# mcu.net
KiCad netlist of a schematic drawn in Altium Designer
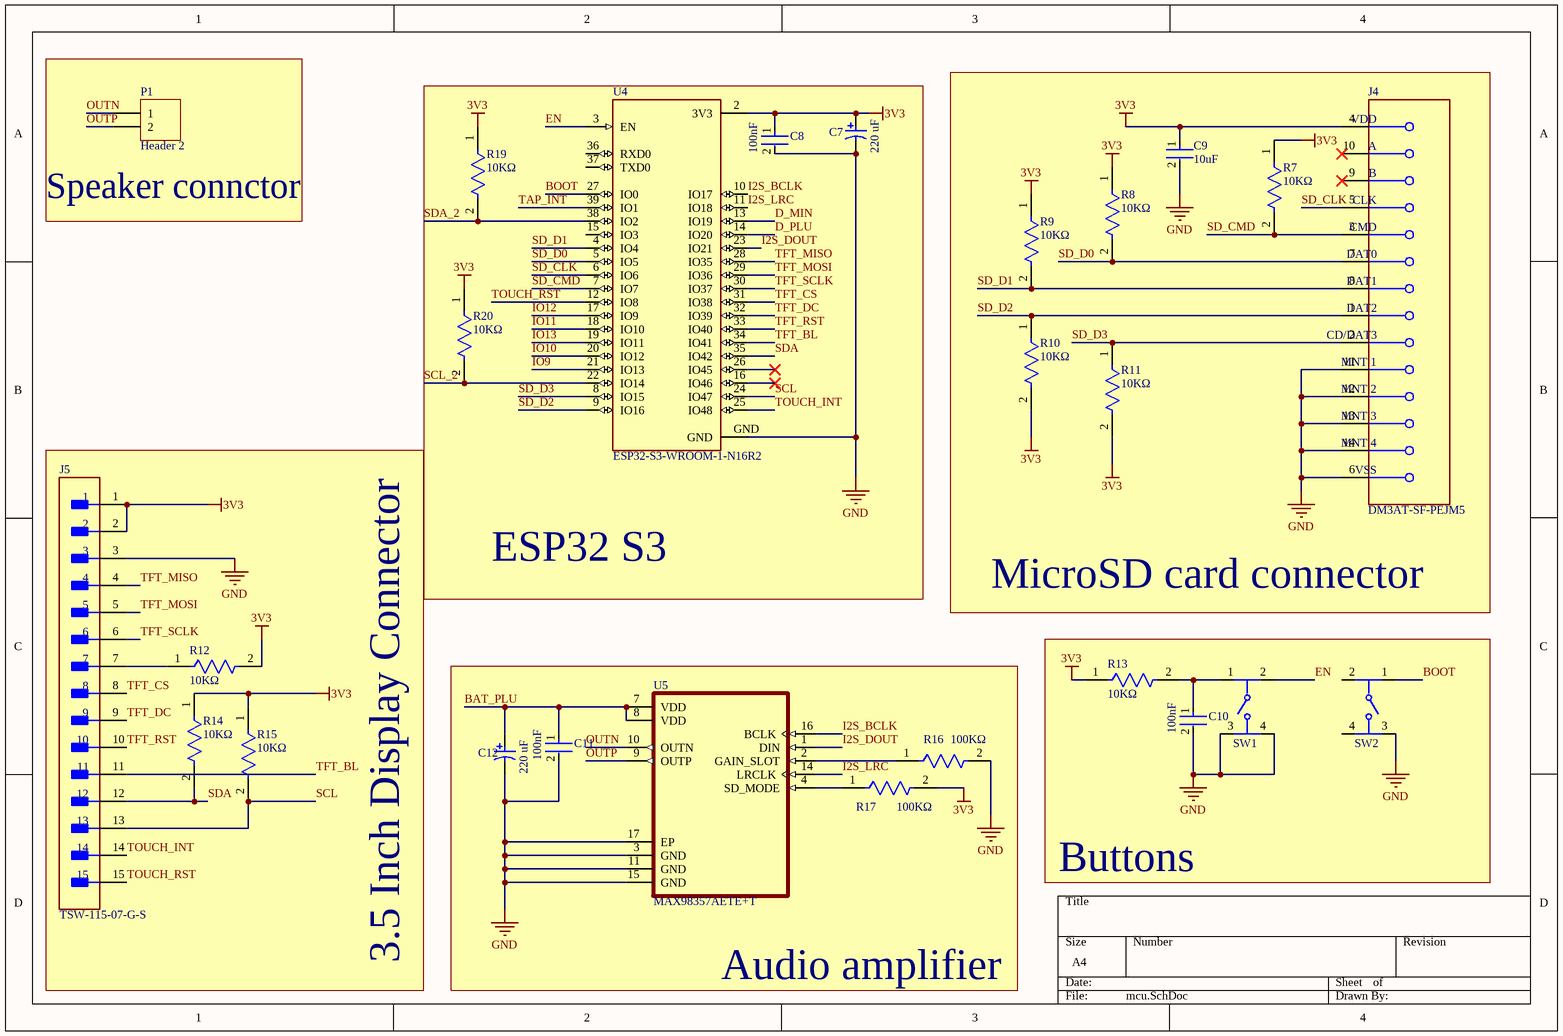
[diagram p0: mcu.SchDoc]

(export (version "E")
  (design (tool "Eeschema 10.0.6"))
  (components
    (comp (ref "C7")
      (value "UUD1V221MNL1GS")
      (footprint "NIC-CAPA2-8X10_V")
      (fields
        (field (name "RATED CAPACITANCE") "220 uF")
        (field (name "MANUFACTURER") "Nichicon")
        (field (name "LCSC PART") "C2836441")
      )
      (libsource (lib "Altium Content Vault") (part "NIC-CAP-P-2"))
    )
    (comp (ref "C8")
      (value "CC0805KKX7RYBB104")
      (footprint "FP-CC0805-EB-IPC_B")
      (description "CC0805KKX7RYBB104 Capacitor Ceramic 0.01uF 250V X7R 10% 0805 T/R")
      (fields
        (field (name "TOLERANCE") "10%")
        (field (name "CAPACITANCE") "100nF")
        (field (name "LCSC PART") "C28233")
      )
      (libsource (lib "Altium Content Vault") (part "b4654b650e69147ec39a6b967a45e02"))
    )
    (comp (ref "C9")
      (value "C0805C106J8RACAUTO")
      (footprint "FP-C0805C106J8RACAUTO-IPC_B")
      (description "CAP CER 10UF 10V X7R 0805")
      (fields
        (field (name "CAPACITANCE") "10uF")
        (field (name "TOLERANCE") "5%")
        (field (name "LCSC PART") "C15850")
      )
      (libsource (lib "Altium Content Vault") (part "02cd4be3c70576c341d710602a673aa"))
    )
    (comp (ref "C10")
      (value "CC0805KKX7RYBB104")
      (footprint "FP-CC0805-EB-IPC_B")
      (description "CC0805KKX7RYBB104 Capacitor Ceramic 0.01uF 250V X7R 10% 0805 T/R")
      (fields
        (field (name "TOLERANCE") "10%")
        (field (name "CAPACITANCE") "100nF")
        (field (name "LCSC PART") "C28233")
      )
      (libsource (lib "Altium Content Vault") (part "b4654b650e69147ec39a6b967a45e02"))
    )
    (comp (ref "C11")
      (value "CC0805KKX7RYBB104")
      (footprint "FP-CC0805-EB-IPC_B")
      (description "CC0805KKX7RYBB104 Capacitor Ceramic 0.01uF 250V X7R 10% 0805 T/R")
      (fields
        (field (name "TOLERANCE") "10%")
        (field (name "CAPACITANCE") "100nF")
        (field (name "LCSC PART") "C28233")
      )
      (libsource (lib "Altium Content Vault") (part "b4654b650e69147ec39a6b967a45e02"))
    )
    (comp (ref "C12")
      (value "UUD1V221MNL1GS")
      (footprint "NIC-CAPA2-8X10_V")
      (fields
        (field (name "RATED CAPACITANCE") "220 uF")
        (field (name "MANUFACTURER") "Nichicon")
        (field (name "LCSC PART") "C2836441")
      )
      (libsource (lib "Altium Content Vault") (part "NIC-CAP-P-2"))
    )
    (comp (ref "J4")
      (value "DM3AT-SF-PEJM5")
      (footprint "FP-DM3AT-SF-PEJM5-MFG")
      (description "CONN MICRO SD CARD PUSH-PUSH R/A")
      (fields (field (name "LCSC PART") "C114218"))
      (libsource (lib "Altium Content Vault") (part "a4e64ec0820c4377148bc1329e4c440"))
    )
    (comp (ref "J5")
      (value "TSW-115-07-G-S")
      (footprint "FP-TSW-115-07-G-S-MFG")
      (description "CONN HEADER VERT 15POS 2.54MM")
      (fields
        (field (name "OCTOPART") "https://octopart.com/tsw-115-07-g-s-samtec-272210")
        (field (name "MANUFACTURER") "SAMTEC")
      )
      (libsource (lib "Altium Content Vault") (part "9e54aee09c46527fb07af492d4d8164"))
    )
    (comp (ref "P1")
      (value "Header 2")
      (footprint "HDR1X2")
      (description "Header, 2-Pin")
      (fields (field (name "LCSC PART") "C32713268") (field (name "PUBLISHER") "Altium Limited"))
      (libsource (lib "Miscellaneous Connectors") (part "Header 2"))
    )
    (comp (ref "R7")
      (value "10KΩ")
      (footprint "FP-RT0805-IPC_B")
      (description "RES SMD 10K OHM 1% 1/8W 0805")
      (fields
        (field (name "OCTOPART") "https://octopart.com/rt0805frd0710kl-yageo-71399701")
        (field (name "TOLERANCE") "0.0001")
      )
      (libsource (lib "Altium Content Vault") (part "1029c3af85768c4190bb7ad29bc67b5"))
    )
    (comp (ref "R8")
      (value "10KΩ")
      (footprint "FP-RT0805-IPC_B")
      (description "RES SMD 10K OHM 1% 1/8W 0805")
      (fields
        (field (name "OCTOPART") "https://octopart.com/rt0805frd0710kl-yageo-71399701")
        (field (name "TOLERANCE") "0.0001")
      )
      (libsource (lib "Altium Content Vault") (part "1029c3af85768c4190bb7ad29bc67b5"))
    )
    (comp (ref "R9")
      (value "10KΩ")
      (footprint "FP-RT0805-IPC_B")
      (description "RES SMD 10K OHM 1% 1/8W 0805")
      (fields
        (field (name "OCTOPART") "https://octopart.com/rt0805frd0710kl-yageo-71399701")
        (field (name "TOLERANCE") "0.0001")
      )
      (libsource (lib "Altium Content Vault") (part "1029c3af85768c4190bb7ad29bc67b5"))
    )
    (comp (ref "R10")
      (value "10KΩ")
      (footprint "FP-RT0805-IPC_B")
      (description "RES SMD 10K OHM 1% 1/8W 0805")
      (fields
        (field (name "OCTOPART") "https://octopart.com/rt0805frd0710kl-yageo-71399701")
        (field (name "TOLERANCE") "0.0001")
      )
      (libsource (lib "Altium Content Vault") (part "1029c3af85768c4190bb7ad29bc67b5"))
    )
    (comp (ref "R11")
      (value "10KΩ")
      (footprint "FP-RT0805-IPC_B")
      (description "RES SMD 10K OHM 1% 1/8W 0805")
      (fields
        (field (name "OCTOPART") "https://octopart.com/rt0805frd0710kl-yageo-71399701")
        (field (name "TOLERANCE") "0.0001")
      )
      (libsource (lib "Altium Content Vault") (part "1029c3af85768c4190bb7ad29bc67b5"))
    )
    (comp (ref "R12")
      (value "10KΩ")
      (footprint "FP-RT0805-IPC_B")
      (description "RES SMD 10K OHM 1% 1/8W 0805")
      (fields
        (field (name "OCTOPART") "https://octopart.com/rt0805frd0710kl-yageo-71399701")
        (field (name "TOLERANCE") "0.0001")
      )
      (libsource (lib "Altium Content Vault") (part "1029c3af85768c4190bb7ad29bc67b5"))
    )
    (comp (ref "R13")
      (value "10KΩ")
      (footprint "FP-RT0805-IPC_B")
      (description "RES SMD 10K OHM 1% 1/8W 0805")
      (fields
        (field (name "OCTOPART") "https://octopart.com/rt0805frd0710kl-yageo-71399701")
        (field (name "TOLERANCE") "0.0001")
      )
      (libsource (lib "Altium Content Vault") (part "1029c3af85768c4190bb7ad29bc67b5"))
    )
    (comp (ref "R14")
      (value "10KΩ")
      (footprint "FP-RT0805-IPC_B")
      (description "RES SMD 10K OHM 1% 1/8W 0805")
      (fields
        (field (name "OCTOPART") "https://octopart.com/rt0805frd0710kl-yageo-71399701")
        (field (name "TOLERANCE") "0.0001")
      )
      (libsource (lib "Altium Content Vault") (part "1029c3af85768c4190bb7ad29bc67b5"))
    )
    (comp (ref "R15")
      (value "10KΩ")
      (footprint "FP-RT0805-IPC_B")
      (description "RES SMD 10K OHM 1% 1/8W 0805")
      (fields
        (field (name "OCTOPART") "https://octopart.com/rt0805frd0710kl-yageo-71399701")
        (field (name "TOLERANCE") "0.0001")
      )
      (libsource (lib "Altium Content Vault") (part "1029c3af85768c4190bb7ad29bc67b5"))
    )
    (comp (ref "R16")
      (value "100KΩ")
      (footprint "FP-RT0805-MFG")
      (description "RES SMD 100K OHM 0.5% 1/8W 0805")
      (fields
        (field (name "MANUFACTURER") "Yageo")
        (field (name "OCTOPART") "https://octopart.com/rt0805drd07100kl-yageo-1251654")
      )
      (libsource (lib "Altium Content Vault") (part "1029c3af85768c4190bb7ad29bc67b5"))
    )
    (comp (ref "R17")
      (value "100KΩ")
      (footprint "FP-RT0805-MFG")
      (description "RES SMD 100K OHM 0.5% 1/8W 0805")
      (fields
        (field (name "MANUFACTURER") "Yageo")
        (field (name "OCTOPART") "https://octopart.com/rt0805drd07100kl-yageo-1251654")
      )
      (libsource (lib "Altium Content Vault") (part "1029c3af85768c4190bb7ad29bc67b5"))
    )
    (comp (ref "R19")
      (value "10KΩ")
      (footprint "FP-RT0805-IPC_B")
      (description "RES SMD 10K OHM 1% 1/8W 0805")
      (fields
        (field (name "OCTOPART") "https://octopart.com/rt0805frd0710kl-yageo-71399701")
        (field (name "TOLERANCE") "0.0001")
      )
      (libsource (lib "Altium Content Vault") (part "1029c3af85768c4190bb7ad29bc67b5"))
    )
    (comp (ref "R20")
      (value "10KΩ")
      (footprint "FP-RT0805-IPC_B")
      (description "RES SMD 10K OHM 1% 1/8W 0805")
      (fields
        (field (name "OCTOPART") "https://octopart.com/rt0805frd0710kl-yageo-71399701")
        (field (name "TOLERANCE") "0.0001")
      )
      (libsource (lib "Altium Content Vault") (part "1029c3af85768c4190bb7ad29bc67b5"))
    )
    (comp (ref "SW1")
      (value "2-1977223-2")
      (footprint "FP-2-1977223-2-MFG")
      (description "SWITCH TACTILE SPST-NO 0.05A 24V")
      (fields (field (name "LCSC PART") "C557615"))
      (libsource (lib "Altium Content Vault") (part "b8895f3f4cefb76e1819d2863dba89b"))
    )
    (comp (ref "SW2")
      (value "2-1977223-2")
      (footprint "FP-2-1977223-2-MFG")
      (description "SWITCH TACTILE SPST-NO 0.05A 24V")
      (fields (field (name "LCSC PART") "C557615"))
      (libsource (lib "Altium Content Vault") (part "b8895f3f4cefb76e1819d2863dba89b"))
    )
    (comp (ref "U4")
      (value "ESP32-S3-WROOM-1-N16R2")
      (footprint "XCVR_ESP32-S3-WROOM-1-N16R2")
      (description "Bluetooth, WiFi 802.11b/g/n, Bluetooth v5.0 Transceiver Module 2.4GHz PCB Trace Surface Mount")
      (fields (field (name "MF") "Espressif Systems") (field (name "MP") "ESP32S3WROOM1N16R2"))
      (libsource (lib "ESP32-S3-WROOM-1-N16R2") (part "ESP32-S3-WROOM-1-N16R2"))
    )
    (comp (ref "U5")
      (value "MAX98357AETE+T")
      (footprint "QFN50P300X300X80-17N")
      (description "Tiny, Low-Cost, PCM Class D Amplifier with Class AB Performance")
      (fields (field (name "MF") "Analog Devices") (field (name "LCSC PART") "C910544"))
      (libsource (lib "MAX98357AETE_T") (part "MAX98357AETE+T"))
    )
  )
  (nets
    (net (code "1") (name "/BAT_PLU") (class "Default")
      (node (ref "C11") (pin "1") (pinfunction "1_1") (pintype "passive"))
      (node (ref "C12") (pin "1") (pinfunction "1_1") (pintype "passive"))
      (node (ref "U5") (pin "7") (pinfunction "VDD_7") (pintype "power_in"))
      (node (ref "U5") (pin "8") (pinfunction "VDD_8") (pintype "power_in"))
    )
    (net (code "2") (name "/BOOT") (class "Default")
      (node (ref "SW2") (pin "1") (pinfunction "1_1") (pintype "passive"))
      (node (ref "U4") (pin "27") (pinfunction "IO0_27") (pintype "bidirectional"))
    )
    (net (code "3") (name "/D_MIN") (class "Default")
      (node (ref "U4") (pin "13") (pinfunction "IO19_13") (pintype "bidirectional"))
    )
    (net (code "4") (name "/D_PLU") (class "Default")
      (node (ref "U4") (pin "14") (pinfunction "IO20_14") (pintype "bidirectional"))
    )
    (net (code "5") (name "/EN") (class "Default")
      (node (ref "SW1") (pin "2") (pinfunction "2_2") (pintype "passive"))
      (node (ref "U4") (pin "3") (pinfunction "EN_3") (pintype "input"))
    )
    (net (code "6") (name "/I2S_BCLK") (class "Default")
      (node (ref "U4") (pin "10") (pinfunction "IO17_10") (pintype "bidirectional"))
      (node (ref "U5") (pin "16") (pinfunction "BCLK_16") (pintype "input"))
    )
    (net (code "7") (name "/I2S_DOUT") (class "Default")
      (node (ref "U4") (pin "23") (pinfunction "IO21_23") (pintype "bidirectional"))
      (node (ref "U5") (pin "1") (pinfunction "DIN_1") (pintype "input"))
    )
    (net (code "8") (name "/I2S_LRC") (class "Default")
      (node (ref "U4") (pin "11") (pinfunction "IO18_11") (pintype "bidirectional"))
      (node (ref "U5") (pin "14") (pinfunction "LRCLK_14") (pintype "input"))
    )
    (net (code "9") (name "/IO9") (class "Default")
      (node (ref "U4") (pin "21") (pinfunction "IO13_21") (pintype "bidirectional"))
    )
    (net (code "10") (name "/IO10") (class "Default")
      (node (ref "U4") (pin "20") (pinfunction "IO12_20") (pintype "bidirectional"))
    )
    (net (code "11") (name "/IO11") (class "Default")
      (node (ref "U4") (pin "18") (pinfunction "IO10_18") (pintype "bidirectional"))
    )
    (net (code "12") (name "/IO12") (class "Default")
      (node (ref "U4") (pin "17") (pinfunction "IO9_17") (pintype "bidirectional"))
    )
    (net (code "13") (name "/IO13") (class "Default")
      (node (ref "U4") (pin "19") (pinfunction "IO11_19") (pintype "bidirectional"))
    )
    (net (code "14") (name "/OUTN") (class "Default")
      (node (ref "P1") (pin "1") (pinfunction "1_1") (pintype "passive"))
      (node (ref "U5") (pin "10") (pinfunction "OUTN_10") (pintype "output"))
    )
    (net (code "15") (name "/OUTP") (class "Default")
      (node (ref "P1") (pin "2") (pinfunction "2_2") (pintype "passive"))
      (node (ref "U5") (pin "9") (pinfunction "OUTP_9") (pintype "output"))
    )
    (net (code "16") (name "/SCL") (class "Default")
      (node (ref "J5") (pin "13") (pinfunction "13_13") (pintype "passive"))
      (node (ref "R15") (pin "2") (pinfunction "2_2") (pintype "passive"))
      (node (ref "U4") (pin "24") (pinfunction "IO47_24") (pintype "bidirectional"))
    )
    (net (code "17") (name "/SCL_2") (class "Default")
      (node (ref "R20") (pin "2") (pinfunction "2_2") (pintype "passive"))
      (node (ref "U4") (pin "22") (pinfunction "IO14_22") (pintype "bidirectional"))
    )
    (net (code "18") (name "/SDA") (class "Default")
      (node (ref "J5") (pin "12") (pinfunction "12_12") (pintype "passive"))
      (node (ref "R14") (pin "2") (pinfunction "2_2") (pintype "passive"))
      (node (ref "U4") (pin "35") (pinfunction "IO42_35") (pintype "bidirectional"))
    )
    (net (code "19") (name "/SDA_2") (class "Default")
      (node (ref "R19") (pin "2") (pinfunction "2_2") (pintype "passive"))
      (node (ref "U4") (pin "38") (pinfunction "IO2_38") (pintype "bidirectional"))
    )
    (net (code "20") (name "/SD_CLK") (class "Default")
      (node (ref "J4") (pin "5") (pinfunction "CLK_5") (pintype "passive"))
      (node (ref "U4") (pin "6") (pinfunction "IO6_6") (pintype "bidirectional"))
    )
    (net (code "21") (name "/SD_CMD") (class "Default")
      (node (ref "J4") (pin "3") (pinfunction "CMD_3") (pintype "passive"))
      (node (ref "R7") (pin "2") (pinfunction "2_2") (pintype "passive"))
      (node (ref "U4") (pin "7") (pinfunction "IO7_7") (pintype "bidirectional"))
    )
    (net (code "22") (name "/SD_D0") (class "Default")
      (node (ref "J4") (pin "7") (pinfunction "DAT0_7") (pintype "passive"))
      (node (ref "R8") (pin "2") (pinfunction "2_2") (pintype "passive"))
      (node (ref "U4") (pin "5") (pinfunction "IO5_5") (pintype "bidirectional"))
    )
    (net (code "23") (name "/SD_D1") (class "Default")
      (node (ref "J4") (pin "8") (pinfunction "DAT1_8") (pintype "passive"))
      (node (ref "R9") (pin "2") (pinfunction "2_2") (pintype "passive"))
      (node (ref "U4") (pin "4") (pinfunction "IO4_4") (pintype "bidirectional"))
    )
    (net (code "24") (name "/SD_D2") (class "Default")
      (node (ref "J4") (pin "1") (pinfunction "DAT2_1") (pintype "passive"))
      (node (ref "R10") (pin "1") (pinfunction "1_1") (pintype "passive"))
      (node (ref "U4") (pin "9") (pinfunction "IO16_9") (pintype "bidirectional"))
    )
    (net (code "25") (name "/SD_D3") (class "Default")
      (node (ref "J4") (pin "2") (pinfunction "CD/DAT3_2") (pintype "passive"))
      (node (ref "R11") (pin "1") (pinfunction "1_1") (pintype "passive"))
      (node (ref "U4") (pin "8") (pinfunction "IO15_8") (pintype "bidirectional"))
    )
    (net (code "26") (name "/TAP_INT") (class "Default")
      (node (ref "U4") (pin "39") (pinfunction "IO1_39") (pintype "bidirectional"))
    )
    (net (code "27") (name "/TFT_BL") (class "Default")
      (node (ref "J5") (pin "11") (pinfunction "11_11") (pintype "passive"))
      (node (ref "U4") (pin "34") (pinfunction "IO41_34") (pintype "bidirectional"))
    )
    (net (code "28") (name "/TFT_CS") (class "Default")
      (node (ref "J5") (pin "8") (pinfunction "8_8") (pintype "passive"))
      (node (ref "U4") (pin "31") (pinfunction "IO38_31") (pintype "bidirectional"))
    )
    (net (code "29") (name "/TFT_DC") (class "Default")
      (node (ref "J5") (pin "9") (pinfunction "9_9") (pintype "passive"))
      (node (ref "U4") (pin "32") (pinfunction "IO39_32") (pintype "bidirectional"))
    )
    (net (code "30") (name "/TFT_MISO") (class "Default")
      (node (ref "J5") (pin "4") (pinfunction "4_4") (pintype "passive"))
      (node (ref "U4") (pin "28") (pinfunction "IO35_28") (pintype "bidirectional"))
    )
    (net (code "31") (name "/TFT_MOSI") (class "Default")
      (node (ref "J5") (pin "5") (pinfunction "5_5") (pintype "passive"))
      (node (ref "U4") (pin "29") (pinfunction "IO36_29") (pintype "bidirectional"))
    )
    (net (code "32") (name "/TFT_RST") (class "Default")
      (node (ref "J5") (pin "10") (pinfunction "10_10") (pintype "passive"))
      (node (ref "U4") (pin "33") (pinfunction "IO40_33") (pintype "bidirectional"))
    )
    (net (code "33") (name "/TFT_SCLK") (class "Default")
      (node (ref "J5") (pin "6") (pinfunction "6_6") (pintype "passive"))
      (node (ref "U4") (pin "30") (pinfunction "IO37_30") (pintype "bidirectional"))
    )
    (net (code "34") (name "/TOUCH_INT") (class "Default")
      (node (ref "J5") (pin "14") (pinfunction "14_14") (pintype "passive"))
      (node (ref "U4") (pin "25") (pinfunction "IO48_25") (pintype "bidirectional"))
    )
    (net (code "35") (name "/TOUCH_RST") (class "Default")
      (node (ref "J5") (pin "15") (pinfunction "15_15") (pintype "passive"))
      (node (ref "U4") (pin "12") (pinfunction "IO8_12") (pintype "bidirectional"))
    )
    (net (code "36") (name "3V3") (class "Default")
      (node (ref "C7") (pin "1") (pinfunction "1_1") (pintype "passive"))
      (node (ref "C8") (pin "1") (pinfunction "1_1") (pintype "passive"))
      (node (ref "C9") (pin "1") (pinfunction "1_1") (pintype "passive"))
      (node (ref "J4") (pin "4") (pinfunction "VDD_4") (pintype "power_in"))
      (node (ref "J5") (pin "1") (pinfunction "1_1") (pintype "passive"))
      (node (ref "J5") (pin "2") (pinfunction "2_2") (pintype "passive"))
      (node (ref "R10") (pin "2") (pinfunction "2_2") (pintype "passive"))
      (node (ref "R11") (pin "2") (pinfunction "2_2") (pintype "passive"))
      (node (ref "R12") (pin "2") (pinfunction "2_2") (pintype "passive"))
      (node (ref "R13") (pin "1") (pinfunction "1_1") (pintype "passive"))
      (node (ref "R14") (pin "1") (pinfunction "1_1") (pintype "passive"))
      (node (ref "R15") (pin "1") (pinfunction "1_1") (pintype "passive"))
      (node (ref "R17") (pin "2") (pinfunction "2_2") (pintype "passive"))
      (node (ref "R19") (pin "1") (pinfunction "1_1") (pintype "passive"))
      (node (ref "R20") (pin "1") (pinfunction "1_1") (pintype "passive"))
      (node (ref "R7") (pin "1") (pinfunction "1_1") (pintype "passive"))
      (node (ref "R8") (pin "1") (pinfunction "1_1") (pintype "passive"))
      (node (ref "R9") (pin "1") (pinfunction "1_1") (pintype "passive"))
      (node (ref "U4") (pin "2") (pinfunction "3V3_2") (pintype "power_in"))
    )
    (net (code "37") (name "GND") (class "Default")
      (node (ref "C10") (pin "2") (pinfunction "2_2") (pintype "passive"))
      (node (ref "C11") (pin "2") (pinfunction "2_2") (pintype "passive"))
      (node (ref "C12") (pin "2") (pinfunction "2_2") (pintype "passive"))
      (node (ref "C7") (pin "2") (pinfunction "2_2") (pintype "passive"))
      (node (ref "C8") (pin "2") (pinfunction "2_2") (pintype "passive"))
      (node (ref "C9") (pin "2") (pinfunction "2_2") (pintype "passive"))
      (node (ref "J4") (pin "11") (pinfunction "MNT_1_11") (pintype "passive"))
      (node (ref "J4") (pin "12") (pinfunction "MNT_2_12") (pintype "passive"))
      (node (ref "J4") (pin "13") (pinfunction "MNT_3_13") (pintype "passive"))
      (node (ref "J4") (pin "14") (pinfunction "MNT_4_14") (pintype "passive"))
      (node (ref "J4") (pin "6") (pinfunction "VSS_6") (pintype "power_in"))
      (node (ref "J5") (pin "3") (pinfunction "3_3") (pintype "passive"))
      (node (ref "R16") (pin "2") (pinfunction "2_2") (pintype "passive"))
      (node (ref "SW1") (pin "3") (pinfunction "3_3") (pintype "passive"))
      (node (ref "SW1") (pin "4") (pinfunction "4_4") (pintype "passive"))
      (node (ref "SW2") (pin "3") (pinfunction "3_3") (pintype "passive"))
      (node (ref "U4") (pin "GND") (pinfunction "GND_GND") (pintype "power_in"))
      (node (ref "U5") (pin "11") (pinfunction "GND_11") (pintype "power_in"))
      (node (ref "U5") (pin "15") (pinfunction "GND_15") (pintype "power_in"))
      (node (ref "U5") (pin "17") (pinfunction "EP_17") (pintype "power_in"))
      (node (ref "U5") (pin "3") (pinfunction "GND_3") (pintype "power_in"))
    )
    (net (code "38") (name "Net-(C10-Pad1)") (class "Default")
      (node (ref "C10") (pin "1") (pinfunction "1_1") (pintype "passive"))
      (node (ref "R13") (pin "2") (pinfunction "2_2") (pintype "passive"))
      (node (ref "SW1") (pin "1") (pinfunction "1_1") (pintype "passive"))
    )
    (net (code "39") (name "Net-(J5-Pad7)") (class "Default")
      (node (ref "J5") (pin "7") (pinfunction "7_7") (pintype "passive"))
      (node (ref "R12") (pin "1") (pinfunction "1_1") (pintype "passive"))
    )
    (net (code "40") (name "Net-(U5-GAIN_SLOT)") (class "Default")
      (node (ref "R16") (pin "1") (pinfunction "1_1") (pintype "passive"))
      (node (ref "U5") (pin "2") (pinfunction "GAIN_SLOT_2") (pintype "input"))
    )
    (net (code "41") (name "Net-(U5-SD_MODE)") (class "Default")
      (node (ref "R17") (pin "1") (pinfunction "1_1") (pintype "passive"))
      (node (ref "U5") (pin "4") (pinfunction "SD_MODE_4") (pintype "input"))
    )
    (net (code "42") (name "unconnected-(J4-A-Pad10)") (class "Default")
      (node (ref "J4") (pin "10") (pinfunction "A_10") (pintype "passive+no_connect"))
    )
    (net (code "43") (name "unconnected-(J4-B-Pad9)") (class "Default")
      (node (ref "J4") (pin "9") (pinfunction "B_9") (pintype "passive+no_connect"))
    )
    (net (code "44") (name "unconnected-(SW2-Pad2)") (class "Default")
      (node (ref "SW2") (pin "2") (pinfunction "2_2") (pintype "passive"))
    )
    (net (code "45") (name "unconnected-(SW2-Pad4)") (class "Default")
      (node (ref "SW2") (pin "4") (pinfunction "4_4") (pintype "passive"))
    )
    (net (code "46") (name "unconnected-(U4-IO3-Pad15)") (class "Default")
      (node (ref "U4") (pin "15") (pinfunction "IO3_15") (pintype "bidirectional"))
    )
    (net (code "47") (name "unconnected-(U4-IO45-Pad26)") (class "Default")
      (node (ref "U4") (pin "26") (pinfunction "IO45_26") (pintype "bidirectional+no_connect"))
    )
    (net (code "48") (name "unconnected-(U4-IO46-Pad16)") (class "Default")
      (node (ref "U4") (pin "16") (pinfunction "IO46_16") (pintype "bidirectional+no_connect"))
    )
    (net (code "49") (name "unconnected-(U4-RXD0-Pad36)") (class "Default")
      (node (ref "U4") (pin "36") (pinfunction "RXD0_36") (pintype "bidirectional"))
    )
    (net (code "50") (name "unconnected-(U4-TXD0-Pad37)") (class "Default")
      (node (ref "U4") (pin "37") (pinfunction "TXD0_37") (pintype "bidirectional"))
    )
  )
)
